# OPS9.net
KiCad netlist of a schematic drawn in EasyEDA Pro
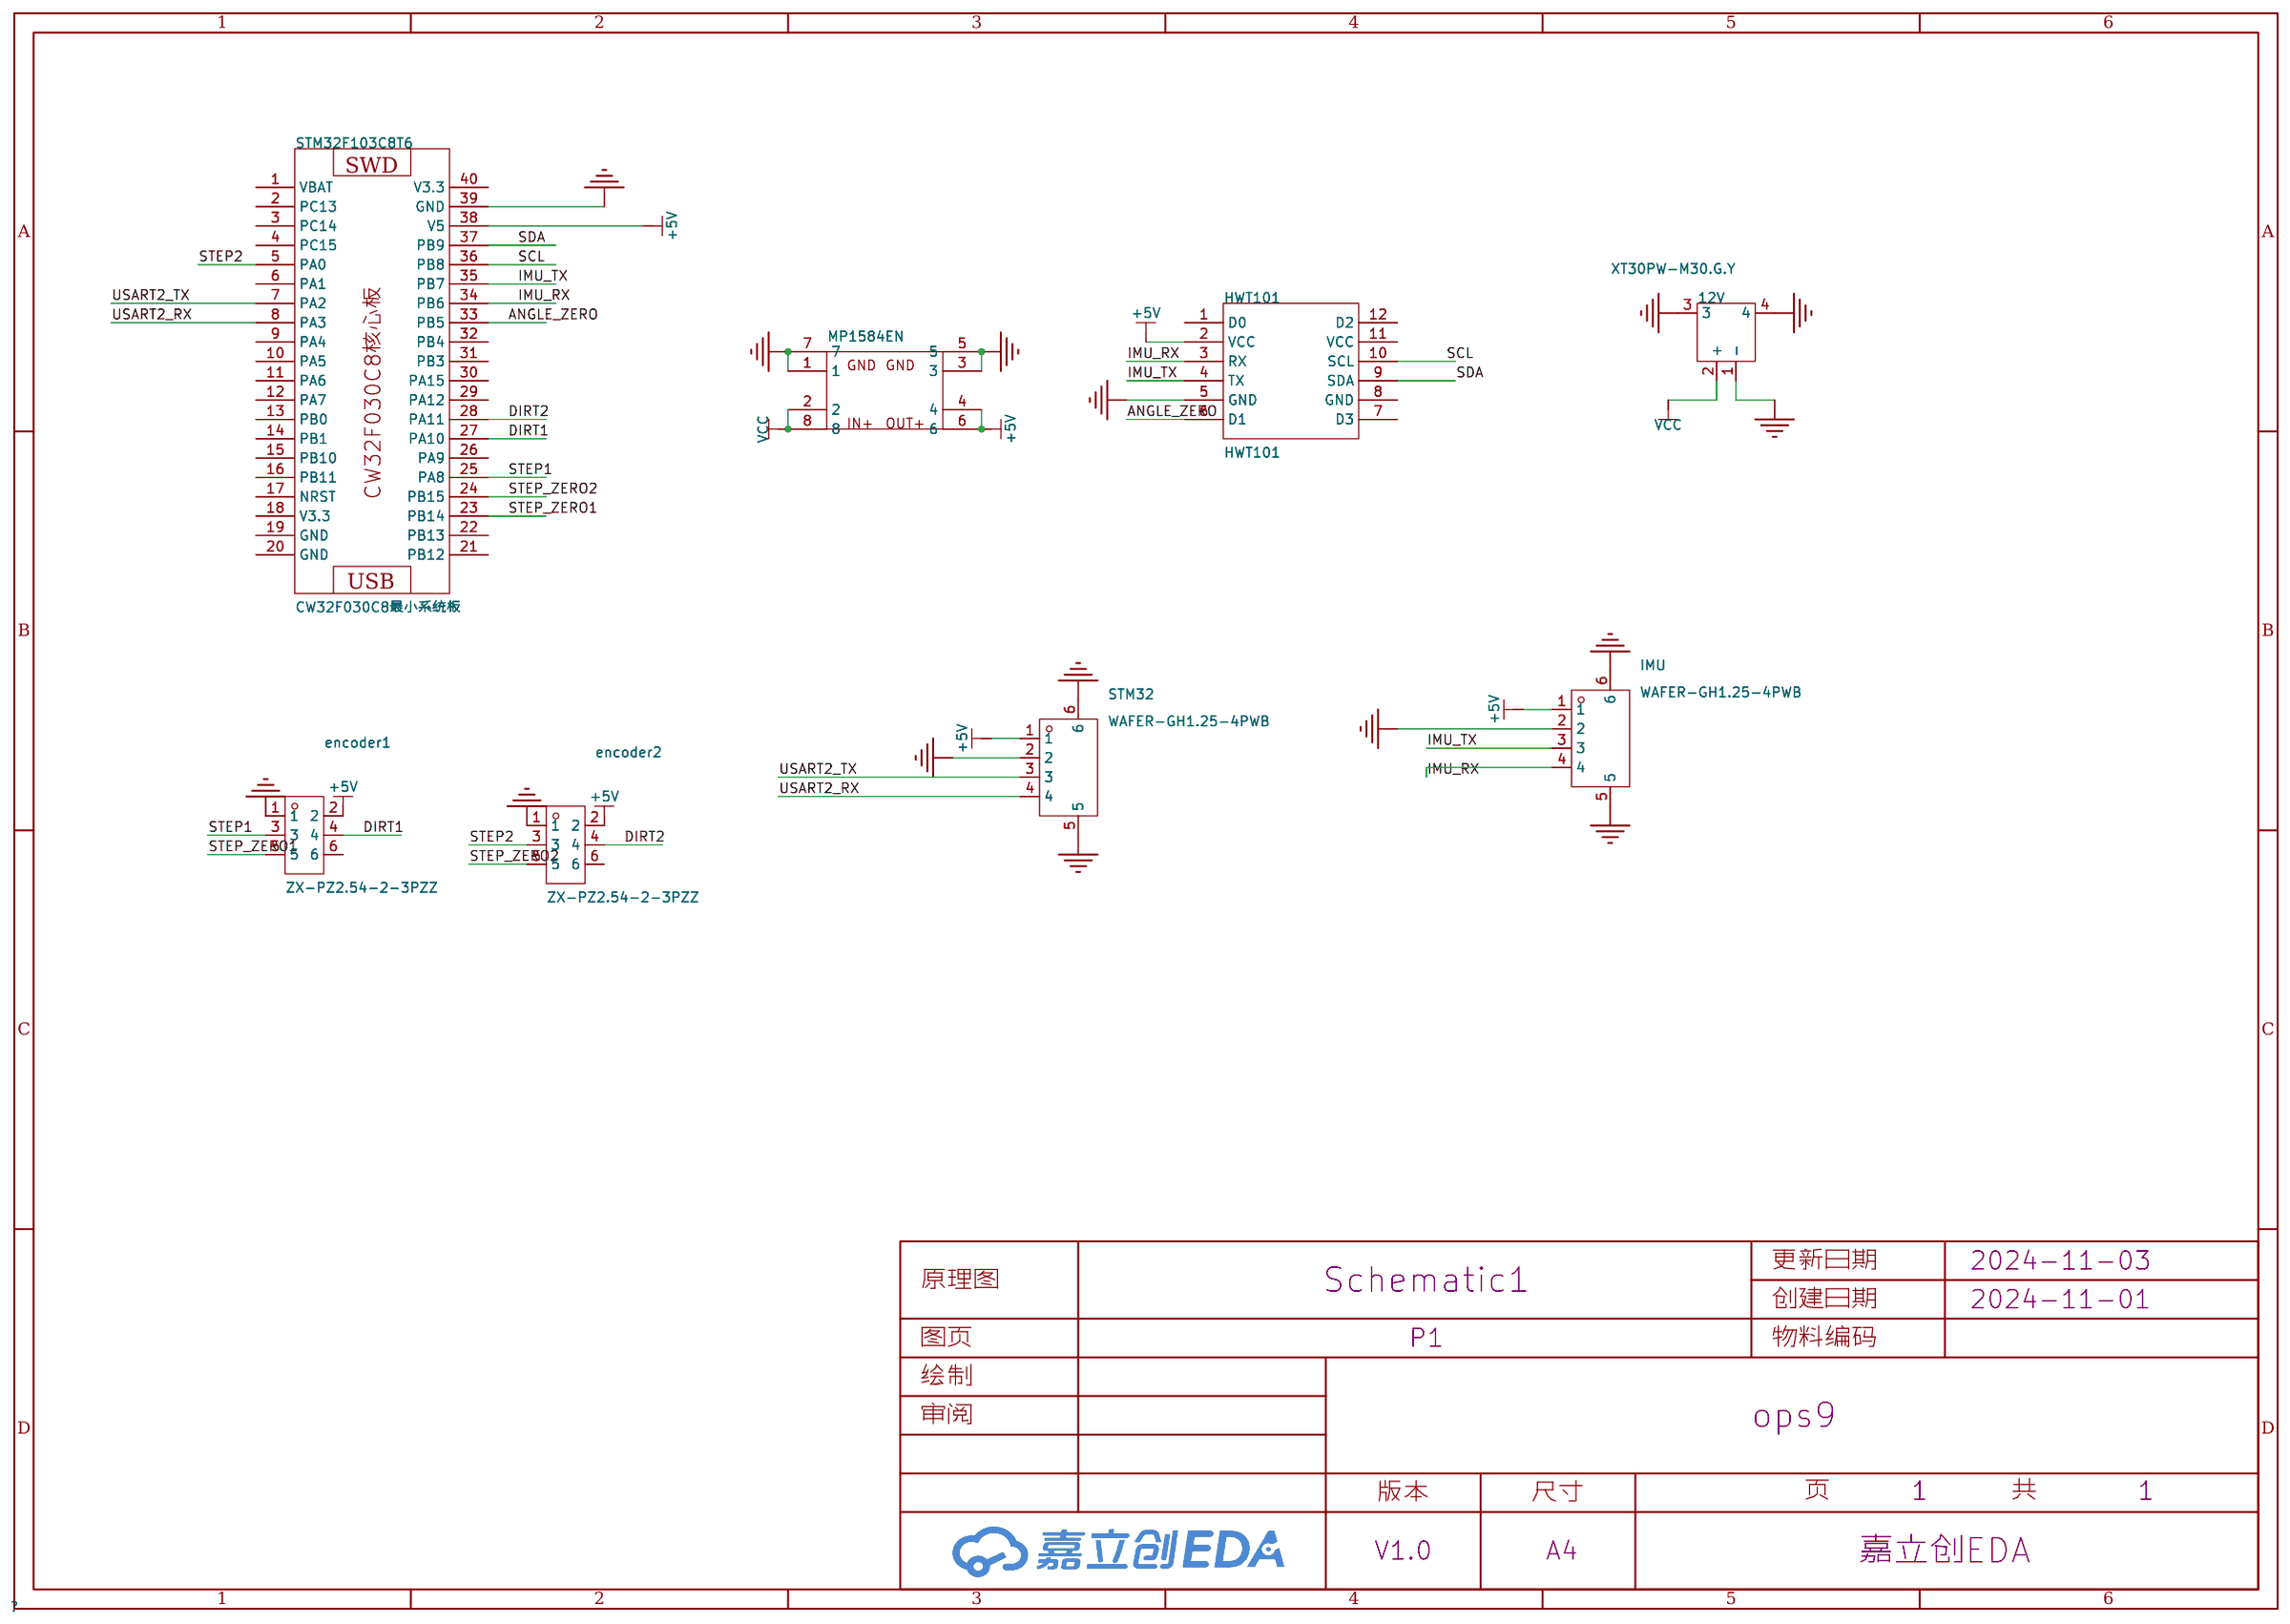
[diagram p0: schematic sheet]

(export (version "E")
  (design (tool "Eeschema 10.0.6"))
  (components
    (comp (ref "12V")
      (value "XT30PW-M30.G.Y")
      (footprint "easyedapro:CONN-TH_XT30PW-M")
      (description "类别:-;类型1:-;")
      (fields (field (name "Manufacturer") "AMASS(艾迈斯)"))
      (libsource (lib "easyedapro") (part "XT30PW-M"))
    )
    (comp (ref "encoder1")
      (value "ZX-PZ2.54-2-3PZZ")
      (footprint "easyedapro:HDR-TH_6P-P2.54-V-M-R2-C3-S2.54-1")
      (fields (field (name "Manufacturer") "Megastar(兆星)"))
      (libsource (lib "easyedapro") (part "ZX-PZ2.54-2-3PZZ"))
    )
    (comp (ref "encoder2")
      (value "ZX-PZ2.54-2-3PZZ")
      (footprint "easyedapro:HDR-TH_6P-P2.54-V-M-R2-C3-S2.54-1")
      (fields (field (name "Manufacturer") "Megastar(兆星)"))
      (libsource (lib "easyedapro") (part "ZX-PZ2.54-2-3PZZ"))
    )
    (comp (ref "HWT101")
      (value "HWT101")
      (footprint "easyedapro:HWT101")
      (libsource (lib "easyedapro") (part "HWT101"))
    )
    (comp (ref "IMU")
      (value "WAFER-GH1.25-4PWB")
      (footprint "easyedapro:CONN-SMD_4P-P1.25_XUNPU_WAFER-GH1.25-4PWB")
      (description "插针结构:1x4P;间距:1.25mm;安装方式:卧贴;参考系列:GH;总PIN数:4P;排数:1;每排PIN数:4;额定电流:1A;工作温度范围:-25°C~+85°C;")
      (fields (field (name "Manufacturer") "XUNPU(讯普)"))
      (libsource (lib "easyedapro") (part "WAFER-GH1.25-4PWB"))
    )
    (comp (ref "MP1584EN")
      (value "~")
      (footprint "easyedapro:LM1584EN")
      (libsource (lib "easyedapro") (part "MP1584EN"))
    )
    (comp (ref "STM32")
      (value "WAFER-GH1.25-4PWB")
      (footprint "easyedapro:CONN-SMD_4P-P1.25_XUNPU_WAFER-GH1.25-4PWB")
      (description "插针结构:1x4P;间距:1.25mm;安装方式:卧贴;参考系列:GH;总PIN数:4P;排数:1;每排PIN数:4;额定电流:1A;工作温度范围:-25°C~+85°C;")
      (fields (field (name "Manufacturer") "XUNPU(讯普)"))
      (libsource (lib "easyedapro") (part "WAFER-GH1.25-4PWB"))
    )
    (comp (ref "STM32F103C8T6")
      (value "CW32F030C8最小系统板")
      (footprint "easyedapro:STM32F103C8T6核心板")
      (fields (field (name "Manufacturer Part") "STM32F103C8T6最小系统模块") (field (name "Manufacturer") "无"))
      (libsource (lib "easyedapro") (part "CW32F030C8最小系统板"))
    )
  )
  (nets
    (net (code "1") (name "+5V") (class "Default")
      (node (ref "HWT101") (pin "2") (pinfunction "VCC_2") (pintype "input"))
      (node (ref "IMU") (pin "1") (pinfunction "1_1") (pintype "unspecified"))
      (node (ref "MP1584EN") (pin "4") (pinfunction "4_4") (pintype "input"))
      (node (ref "MP1584EN") (pin "6") (pinfunction "6_6") (pintype "input"))
      (node (ref "STM32") (pin "1") (pinfunction "1_1") (pintype "unspecified"))
      (node (ref "STM32F103C8T6") (pin "38") (pinfunction "V5_38") (pintype "input"))
      (node (ref "encoder1") (pin "2") (pinfunction "2_2") (pintype "unspecified"))
      (node (ref "encoder2") (pin "2") (pinfunction "2_2") (pintype "unspecified"))
    )
    (net (code "2") (name "/ANGLE_ZERO") (class "Default")
      (node (ref "HWT101") (pin "6") (pinfunction "D1_6") (pintype "input"))
      (node (ref "STM32F103C8T6") (pin "33") (pinfunction "PB5_33") (pintype "bidirectional"))
    )
    (net (code "3") (name "/DIRT1") (class "Default")
      (node (ref "STM32F103C8T6") (pin "27") (pinfunction "PA10_27") (pintype "bidirectional"))
      (node (ref "encoder1") (pin "4") (pinfunction "4_4") (pintype "unspecified"))
    )
    (net (code "4") (name "/DIRT2") (class "Default")
      (node (ref "STM32F103C8T6") (pin "28") (pinfunction "PA11_28") (pintype "bidirectional"))
      (node (ref "encoder2") (pin "4") (pinfunction "4_4") (pintype "unspecified"))
    )
    (net (code "5") (name "/IMU_RX") (class "Default")
      (node (ref "HWT101") (pin "3") (pinfunction "RX_3") (pintype "input"))
      (node (ref "IMU") (pin "4") (pinfunction "4_4") (pintype "unspecified"))
      (node (ref "STM32F103C8T6") (pin "34") (pinfunction "PB6_34") (pintype "bidirectional"))
    )
    (net (code "6") (name "/IMU_TX") (class "Default")
      (node (ref "HWT101") (pin "4") (pinfunction "TX_4") (pintype "input"))
      (node (ref "IMU") (pin "3") (pinfunction "3_3") (pintype "unspecified"))
      (node (ref "STM32F103C8T6") (pin "35") (pinfunction "PB7_35") (pintype "bidirectional"))
    )
    (net (code "7") (name "/SCL") (class "Default")
      (node (ref "HWT101") (pin "10") (pinfunction "SCL_10") (pintype "input"))
      (node (ref "STM32F103C8T6") (pin "36") (pinfunction "PB8_36") (pintype "bidirectional"))
    )
    (net (code "8") (name "/SDA") (class "Default")
      (node (ref "HWT101") (pin "9") (pinfunction "SDA_9") (pintype "input"))
      (node (ref "STM32F103C8T6") (pin "37") (pinfunction "PB9_37") (pintype "bidirectional"))
    )
    (net (code "9") (name "/STEP1") (class "Default")
      (node (ref "STM32F103C8T6") (pin "25") (pinfunction "PA8_25") (pintype "bidirectional"))
      (node (ref "encoder1") (pin "3") (pinfunction "3_3") (pintype "unspecified"))
    )
    (net (code "10") (name "/STEP2") (class "Default")
      (node (ref "STM32F103C8T6") (pin "5") (pinfunction "PA0_5") (pintype "bidirectional"))
      (node (ref "encoder2") (pin "3") (pinfunction "3_3") (pintype "unspecified"))
    )
    (net (code "11") (name "/STEP_ZERO1") (class "Default")
      (node (ref "STM32F103C8T6") (pin "23") (pinfunction "PB14_23") (pintype "bidirectional"))
      (node (ref "encoder1") (pin "5") (pinfunction "5_5") (pintype "unspecified"))
    )
    (net (code "12") (name "/STEP_ZERO2") (class "Default")
      (node (ref "STM32F103C8T6") (pin "24") (pinfunction "PB15_24") (pintype "bidirectional"))
      (node (ref "encoder2") (pin "5") (pinfunction "5_5") (pintype "unspecified"))
    )
    (net (code "13") (name "/USART2_RX") (class "Default")
      (node (ref "STM32") (pin "4") (pinfunction "4_4") (pintype "unspecified"))
      (node (ref "STM32F103C8T6") (pin "8") (pinfunction "PA3_8") (pintype "bidirectional"))
    )
    (net (code "14") (name "/USART2_TX") (class "Default")
      (node (ref "STM32") (pin "3") (pinfunction "3_3") (pintype "unspecified"))
      (node (ref "STM32F103C8T6") (pin "7") (pinfunction "PA2_7") (pintype "bidirectional"))
    )
    (net (code "15") (name "GND") (class "Default")
      (node (ref "12V") (pin "1") (pinfunction "-_1") (pintype "unspecified"))
      (node (ref "12V") (pin "3") (pinfunction "3_3") (pintype "unspecified"))
      (node (ref "12V") (pin "4") (pinfunction "4_4") (pintype "unspecified"))
      (node (ref "HWT101") (pin "5") (pinfunction "GND_5") (pintype "input"))
      (node (ref "IMU") (pin "2") (pinfunction "2_2") (pintype "unspecified"))
      (node (ref "IMU") (pin "5") (pinfunction "5_5") (pintype "unspecified"))
      (node (ref "IMU") (pin "6") (pinfunction "6_6") (pintype "unspecified"))
      (node (ref "MP1584EN") (pin "1") (pinfunction "1_1") (pintype "input"))
      (node (ref "MP1584EN") (pin "3") (pinfunction "3_3") (pintype "input"))
      (node (ref "MP1584EN") (pin "5") (pinfunction "5_5") (pintype "input"))
      (node (ref "MP1584EN") (pin "7") (pinfunction "7_7") (pintype "input"))
      (node (ref "STM32") (pin "2") (pinfunction "2_2") (pintype "unspecified"))
      (node (ref "STM32") (pin "5") (pinfunction "5_5") (pintype "unspecified"))
      (node (ref "STM32") (pin "6") (pinfunction "6_6") (pintype "unspecified"))
      (node (ref "STM32F103C8T6") (pin "39") (pinfunction "GND_39") (pintype "input"))
      (node (ref "encoder1") (pin "1") (pinfunction "1_1") (pintype "unspecified"))
      (node (ref "encoder2") (pin "1") (pinfunction "1_1") (pintype "unspecified"))
    )
    (net (code "16") (name "VCC") (class "Default")
      (node (ref "12V") (pin "2") (pinfunction "+_2") (pintype "unspecified"))
      (node (ref "MP1584EN") (pin "2") (pinfunction "2_2") (pintype "input"))
      (node (ref "MP1584EN") (pin "8") (pinfunction "8_8") (pintype "input"))
    )
    (net (code "17") (name "unconnected-(HWT101-D0-Pad1)") (class "Default")
      (node (ref "HWT101") (pin "1") (pinfunction "D0_1") (pintype "input"))
    )
    (net (code "18") (name "unconnected-(HWT101-D2-Pad12)") (class "Default")
      (node (ref "HWT101") (pin "12") (pinfunction "D2_12") (pintype "input"))
    )
    (net (code "19") (name "unconnected-(HWT101-D3-Pad7)") (class "Default")
      (node (ref "HWT101") (pin "7") (pinfunction "D3_7") (pintype "input"))
    )
    (net (code "20") (name "unconnected-(HWT101-GND-Pad8)") (class "Default")
      (node (ref "HWT101") (pin "8") (pinfunction "GND_8") (pintype "input"))
    )
    (net (code "21") (name "unconnected-(HWT101-VCC-Pad11)") (class "Default")
      (node (ref "HWT101") (pin "11") (pinfunction "VCC_11") (pintype "input"))
    )
    (net (code "22") (name "unconnected-(STM32F103C8T6-GND-Pad19)") (class "Default")
      (node (ref "STM32F103C8T6") (pin "19") (pinfunction "GND_19") (pintype "input"))
    )
    (net (code "23") (name "unconnected-(STM32F103C8T6-GND-Pad20)") (class "Default")
      (node (ref "STM32F103C8T6") (pin "20") (pinfunction "GND_20") (pintype "input"))
    )
    (net (code "24") (name "unconnected-(STM32F103C8T6-NRST-Pad17)") (class "Default")
      (node (ref "STM32F103C8T6") (pin "17") (pinfunction "NRST_17") (pintype "bidirectional"))
    )
    (net (code "25") (name "unconnected-(STM32F103C8T6-PA1-Pad6)") (class "Default")
      (node (ref "STM32F103C8T6") (pin "6") (pinfunction "PA1_6") (pintype "bidirectional"))
    )
    (net (code "26") (name "unconnected-(STM32F103C8T6-PA4-Pad9)") (class "Default")
      (node (ref "STM32F103C8T6") (pin "9") (pinfunction "PA4_9") (pintype "bidirectional"))
    )
    (net (code "27") (name "unconnected-(STM32F103C8T6-PA5-Pad10)") (class "Default")
      (node (ref "STM32F103C8T6") (pin "10") (pinfunction "PA5_10") (pintype "bidirectional"))
    )
    (net (code "28") (name "unconnected-(STM32F103C8T6-PA6-Pad11)") (class "Default")
      (node (ref "STM32F103C8T6") (pin "11") (pinfunction "PA6_11") (pintype "bidirectional"))
    )
    (net (code "29") (name "unconnected-(STM32F103C8T6-PA7-Pad12)") (class "Default")
      (node (ref "STM32F103C8T6") (pin "12") (pinfunction "PA7_12") (pintype "bidirectional"))
    )
    (net (code "30") (name "unconnected-(STM32F103C8T6-PA9-Pad26)") (class "Default")
      (node (ref "STM32F103C8T6") (pin "26") (pinfunction "PA9_26") (pintype "bidirectional"))
    )
    (net (code "31") (name "unconnected-(STM32F103C8T6-PA12-Pad29)") (class "Default")
      (node (ref "STM32F103C8T6") (pin "29") (pinfunction "PA12_29") (pintype "bidirectional"))
    )
    (net (code "32") (name "unconnected-(STM32F103C8T6-PA15-Pad30)") (class "Default")
      (node (ref "STM32F103C8T6") (pin "30") (pinfunction "PA15_30") (pintype "bidirectional"))
    )
    (net (code "33") (name "unconnected-(STM32F103C8T6-PB0-Pad13)") (class "Default")
      (node (ref "STM32F103C8T6") (pin "13") (pinfunction "PB0_13") (pintype "bidirectional"))
    )
    (net (code "34") (name "unconnected-(STM32F103C8T6-PB1-Pad14)") (class "Default")
      (node (ref "STM32F103C8T6") (pin "14") (pinfunction "PB1_14") (pintype "bidirectional"))
    )
    (net (code "35") (name "unconnected-(STM32F103C8T6-PB3-Pad31)") (class "Default")
      (node (ref "STM32F103C8T6") (pin "31") (pinfunction "PB3_31") (pintype "bidirectional"))
    )
    (net (code "36") (name "unconnected-(STM32F103C8T6-PB4-Pad32)") (class "Default")
      (node (ref "STM32F103C8T6") (pin "32") (pinfunction "PB4_32") (pintype "bidirectional"))
    )
    (net (code "37") (name "unconnected-(STM32F103C8T6-PB10-Pad15)") (class "Default")
      (node (ref "STM32F103C8T6") (pin "15") (pinfunction "PB10_15") (pintype "bidirectional"))
    )
    (net (code "38") (name "unconnected-(STM32F103C8T6-PB11-Pad16)") (class "Default")
      (node (ref "STM32F103C8T6") (pin "16") (pinfunction "PB11_16") (pintype "bidirectional"))
    )
    (net (code "39") (name "unconnected-(STM32F103C8T6-PB12-Pad21)") (class "Default")
      (node (ref "STM32F103C8T6") (pin "21") (pinfunction "PB12_21") (pintype "bidirectional"))
    )
    (net (code "40") (name "unconnected-(STM32F103C8T6-PB13-Pad22)") (class "Default")
      (node (ref "STM32F103C8T6") (pin "22") (pinfunction "PB13_22") (pintype "bidirectional"))
    )
    (net (code "41") (name "unconnected-(STM32F103C8T6-PC13-Pad2)") (class "Default")
      (node (ref "STM32F103C8T6") (pin "2") (pinfunction "PC13_2") (pintype "bidirectional"))
    )
    (net (code "42") (name "unconnected-(STM32F103C8T6-PC14-Pad3)") (class "Default")
      (node (ref "STM32F103C8T6") (pin "3") (pinfunction "PC14_3") (pintype "bidirectional"))
    )
    (net (code "43") (name "unconnected-(STM32F103C8T6-PC15-Pad4)") (class "Default")
      (node (ref "STM32F103C8T6") (pin "4") (pinfunction "PC15_4") (pintype "bidirectional"))
    )
    (net (code "44") (name "unconnected-(STM32F103C8T6-V3.3-Pad18)") (class "Default")
      (node (ref "STM32F103C8T6") (pin "18") (pinfunction "V3.3_18") (pintype "input"))
    )
    (net (code "45") (name "unconnected-(STM32F103C8T6-V3.3-Pad40)") (class "Default")
      (node (ref "STM32F103C8T6") (pin "40") (pinfunction "V3.3_40") (pintype "input"))
    )
    (net (code "46") (name "unconnected-(STM32F103C8T6-VBAT-Pad1)") (class "Default")
      (node (ref "STM32F103C8T6") (pin "1") (pinfunction "VBAT_1") (pintype "input"))
    )
    (net (code "47") (name "unconnected-(encoder1-Pad6)") (class "Default")
      (node (ref "encoder1") (pin "6") (pinfunction "6_6") (pintype "unspecified"))
    )
    (net (code "48") (name "unconnected-(encoder2-Pad6)") (class "Default")
      (node (ref "encoder2") (pin "6") (pinfunction "6_6") (pintype "unspecified"))
    )
  )
)
